# Page12_SOM_Interface.net
KiCad netlist of a schematic drawn in Altium Designer
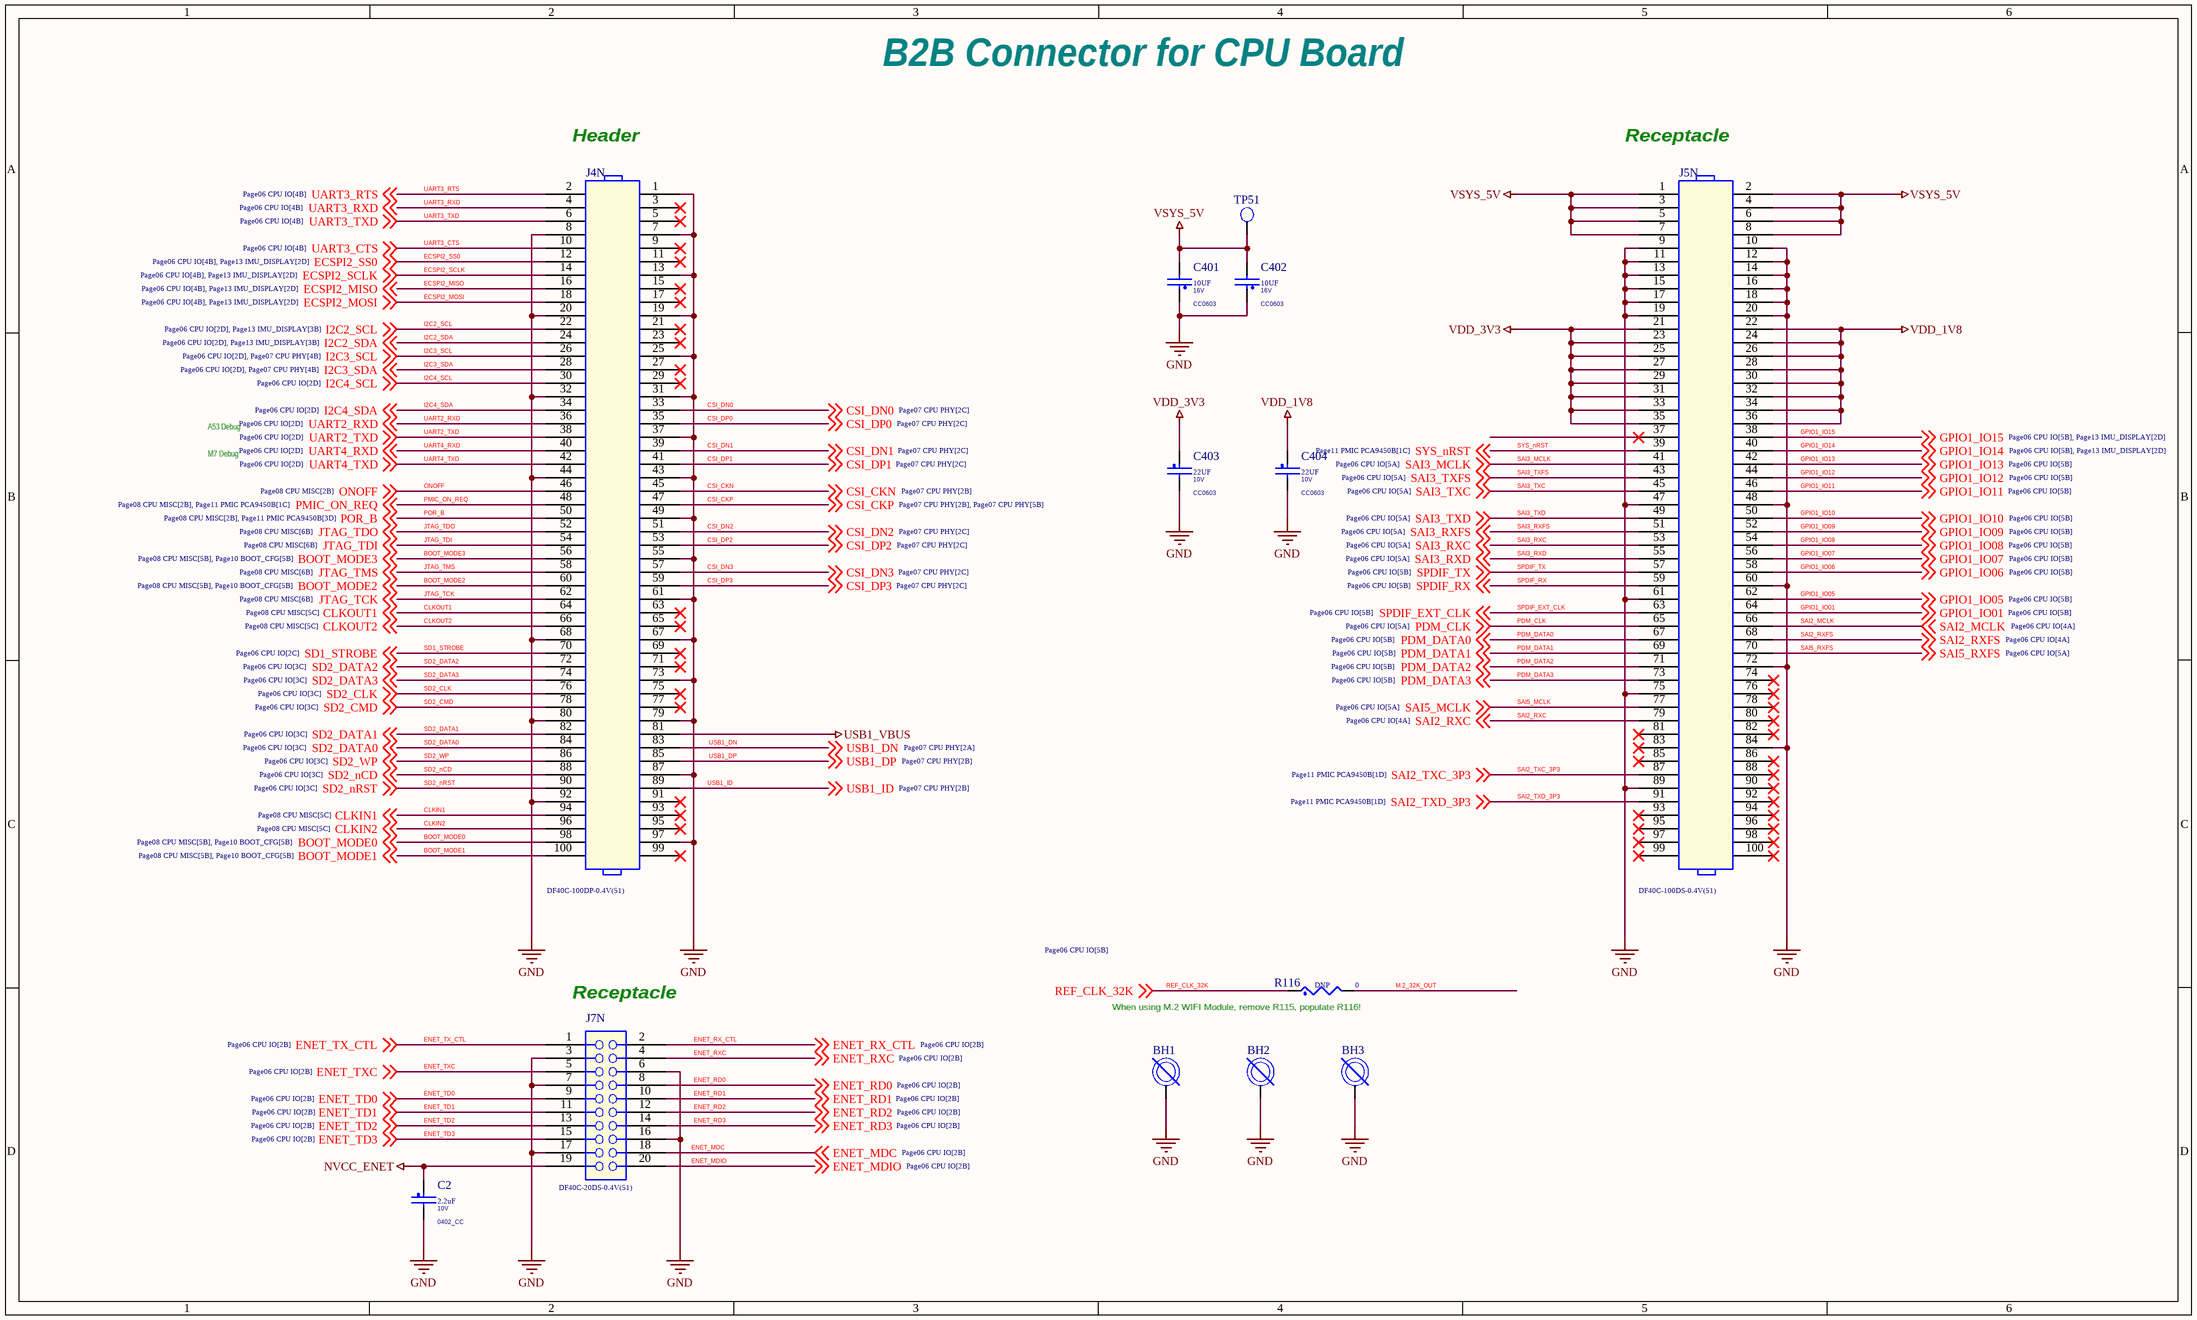
[diagram p0: Page12 SOM Interface.SchDoc]

(export (version "E")
  (design (tool "Eeschema 10.0.6"))
  (components
    (comp (ref "BH1")
      (value "MOUNTING HOLE")
      (footprint "GNDPOINT256")
      (description "MOUNTING HOLE DRILL 109 PAD 200 PLATED TH NO PART TO ORDER")
      (libsource (lib "*") (part "MOUNT_HOLE"))
    )
    (comp (ref "BH2")
      (value "MOUNTING HOLE")
      (footprint "GNDPOINT256")
      (description "MOUNTING HOLE DRILL 109 PAD 200 PLATED TH NO PART TO ORDER")
      (libsource (lib "*") (part "MOUNT_HOLE"))
    )
    (comp (ref "BH3")
      (value "MOUNTING HOLE")
      (footprint "GNDPOINT256")
      (description "MOUNTING HOLE DRILL 109 PAD 200 PLATED TH NO PART TO ORDER")
      (libsource (lib "*") (part "MOUNT_HOLE"))
    )
    (comp (ref "C2")
      (value "2.2uF")
      (footprint "0402_CC")
      (description "CAP CER 2.2uF 10V 10% X5R 0402")
      (fields
        (field (name "TOLERANCE") "10%")
        (field (name "VOLTAGE") "10V")
        (field (name "PCB FOOTPRINT") "0402_CC")
      )
      (libsource (lib "*") (part "CAP_NP"))
    )
    (comp (ref "C401")
      (value "10UF")
      (footprint "0603_CC")
      (description "CAP CER 10.0uF 16V 10% X5R 0603")
      (fields
        (field (name "PCB FOOTPRINT") "CC0603")
        (field (name "TOLERANCE") "10%")
        (field (name "VOLTAGE") "16V")
      )
      (libsource (lib "*") (part "CAP_NP"))
    )
    (comp (ref "C402")
      (value "10UF")
      (footprint "0603_CC")
      (description "CAP CER 10.0uF 16V 10% X5R 0603")
      (fields
        (field (name "PCB FOOTPRINT") "CC0603")
        (field (name "VOLTAGE") "16V")
        (field (name "TOLERANCE") "10%")
      )
      (libsource (lib "*") (part "CAP_NP"))
    )
    (comp (ref "C403")
      (value "22UF")
      (footprint "0603_CC")
      (description "CAP CER 22uF 10V 20% X5R 0603")
      (fields
        (field (name "PCB FOOTPRINT") "CC0603")
        (field (name "VOLTAGE") "10V")
        (field (name "TOLERANCE") "20%")
      )
      (libsource (lib "*") (part "CAP_NP"))
    )
    (comp (ref "C404")
      (value "22UF")
      (footprint "0603_CC")
      (description "CAP CER 22uF 10V 20% X5R 0603")
      (fields
        (field (name "PCB FOOTPRINT") "CC0603")
        (field (name "VOLTAGE") "10V")
        (field (name "TOLERANCE") "20%")
      )
      (libsource (lib "*") (part "CAP_NP"))
    )
    (comp (ref "J4N")
      (value "DF40C-100DP-0.4V(51)")
      (footprint "con100_0p4_21p7x2p05_sm")
      (description "CON 2X50 PLUG SHRD SMT 0.4MM SP 51H AU")
      (libsource (lib "") (part "HDR_2X50_M_1"))
    )
    (comp (ref "J5N")
      (value "DF40C-100DS-0.4V(51)")
      (footprint "con100_0p4_22p8x3p1_sm")
      (description "CON 2X50 SKT SHRD SMT 0.4MM SP 65H AU")
      (libsource (lib "*") (part "HDR_2X50_M"))
    )
    (comp (ref "J7N")
      (value "DF40C-20DS-0.4V(51)")
      (footprint "con20_0p4_6p8x3p1_sm")
      (description "CON 2X10 SKT SHRD SMT 0.4MM SP 63H AU")
      (libsource (lib "*") (part "CONN_HDR_10X2"))
    )
    (comp (ref "R116")
      (value "0")
      (footprint "0402_CC_RES")
      (description "RES MF ZERO OHM 1/16W 5% 0402")
      (fields
        (field (name "ASSY_OPT") "DNP")
        (field (name "VOLTAGE") "1/16W")
        (field (name "TOLERANCE") "5%")
      )
      (libsource (lib "*") (part "RES"))
    )
    (comp (ref "TP51")
      (value "TP_35MIL")
      (footprint "Test Pin")
      (description "TEST POINT PAD .035 SMT, no part to order")
      (libsource (lib "*") (part "T POINT R"))
    )
  )
  (nets
    (net (code "1") (name "/M.2_32K_OUT") (class "Default")
      (node (ref "R116") (pin "2") (pinfunction "2_2") (pintype "passive"))
    )
    (net (code "2") (name "BOOT_MODE0") (class "Default")
      (node (ref "J4N") (pin "98") (pinfunction "98_98") (pintype "passive"))
    )
    (net (code "3") (name "BOOT_MODE1") (class "Default")
      (node (ref "J4N") (pin "100") (pinfunction "100_100") (pintype "passive"))
    )
    (net (code "4") (name "BOOT_MODE2") (class "Default")
      (node (ref "J4N") (pin "60") (pinfunction "60_60") (pintype "passive"))
    )
    (net (code "5") (name "BOOT_MODE3") (class "Default")
      (node (ref "J4N") (pin "56") (pinfunction "56_56") (pintype "passive"))
    )
    (net (code "6") (name "CLKIN1") (class "Default")
      (node (ref "J4N") (pin "94") (pinfunction "94_94") (pintype "passive"))
    )
    (net (code "7") (name "CLKIN2") (class "Default")
      (node (ref "J4N") (pin "96") (pinfunction "96_96") (pintype "passive"))
    )
    (net (code "8") (name "CLKOUT1") (class "Default")
      (node (ref "J4N") (pin "64") (pinfunction "64_64") (pintype "passive"))
    )
    (net (code "9") (name "CLKOUT2") (class "Default")
      (node (ref "J4N") (pin "66") (pinfunction "66_66") (pintype "passive"))
    )
    (net (code "10") (name "CSI_CKN") (class "Default")
      (node (ref "J4N") (pin "45") (pinfunction "45_45") (pintype "passive"))
    )
    (net (code "11") (name "CSI_CKP") (class "Default")
      (node (ref "J4N") (pin "47") (pinfunction "47_47") (pintype "passive"))
    )
    (net (code "12") (name "CSI_DN0") (class "Default")
      (node (ref "J4N") (pin "33") (pinfunction "33_33") (pintype "passive"))
    )
    (net (code "13") (name "CSI_DN1") (class "Default")
      (node (ref "J4N") (pin "39") (pinfunction "39_39") (pintype "passive"))
    )
    (net (code "14") (name "CSI_DN2") (class "Default")
      (node (ref "J4N") (pin "51") (pinfunction "51_51") (pintype "passive"))
    )
    (net (code "15") (name "CSI_DN3") (class "Default")
      (node (ref "J4N") (pin "57") (pinfunction "57_57") (pintype "passive"))
    )
    (net (code "16") (name "CSI_DP0") (class "Default")
      (node (ref "J4N") (pin "35") (pinfunction "35_35") (pintype "passive"))
    )
    (net (code "17") (name "CSI_DP1") (class "Default")
      (node (ref "J4N") (pin "41") (pinfunction "41_41") (pintype "passive"))
    )
    (net (code "18") (name "CSI_DP2") (class "Default")
      (node (ref "J4N") (pin "53") (pinfunction "53_53") (pintype "passive"))
    )
    (net (code "19") (name "CSI_DP3") (class "Default")
      (node (ref "J4N") (pin "59") (pinfunction "59_59") (pintype "passive"))
    )
    (net (code "20") (name "ECSPI2_MISO") (class "Default")
      (node (ref "J4N") (pin "16") (pinfunction "16_16") (pintype "passive"))
    )
    (net (code "21") (name "ECSPI2_MOSI") (class "Default")
      (node (ref "J4N") (pin "18") (pinfunction "18_18") (pintype "passive"))
    )
    (net (code "22") (name "ECSPI2_SCLK") (class "Default")
      (node (ref "J4N") (pin "14") (pinfunction "14_14") (pintype "passive"))
    )
    (net (code "23") (name "ECSPI2_SS0") (class "Default")
      (node (ref "J4N") (pin "12") (pinfunction "12_12") (pintype "passive"))
    )
    (net (code "24") (name "ENET_MDC") (class "Default")
      (node (ref "J7N") (pin "18") (pinfunction "18_18") (pintype "passive"))
    )
    (net (code "25") (name "ENET_MDIO") (class "Default")
      (node (ref "J7N") (pin "20") (pinfunction "20_20") (pintype "passive"))
    )
    (net (code "26") (name "ENET_RD0") (class "Default")
      (node (ref "J7N") (pin "8") (pinfunction "8_8") (pintype "passive"))
    )
    (net (code "27") (name "ENET_RD1") (class "Default")
      (node (ref "J7N") (pin "10") (pinfunction "10_10") (pintype "passive"))
    )
    (net (code "28") (name "ENET_RD2") (class "Default")
      (node (ref "J7N") (pin "12") (pinfunction "12_12") (pintype "passive"))
    )
    (net (code "29") (name "ENET_RD3") (class "Default")
      (node (ref "J7N") (pin "14") (pinfunction "14_14") (pintype "passive"))
    )
    (net (code "30") (name "ENET_RXC") (class "Default")
      (node (ref "J7N") (pin "4") (pinfunction "4_4") (pintype "passive"))
    )
    (net (code "31") (name "ENET_RX_CTL") (class "Default")
      (node (ref "J7N") (pin "2") (pinfunction "2_2") (pintype "passive"))
    )
    (net (code "32") (name "ENET_TD0") (class "Default")
      (node (ref "J7N") (pin "9") (pinfunction "9_9") (pintype "passive"))
    )
    (net (code "33") (name "ENET_TD1") (class "Default")
      (node (ref "J7N") (pin "11") (pinfunction "11_11") (pintype "passive"))
    )
    (net (code "34") (name "ENET_TD2") (class "Default")
      (node (ref "J7N") (pin "13") (pinfunction "13_13") (pintype "passive"))
    )
    (net (code "35") (name "ENET_TD3") (class "Default")
      (node (ref "J7N") (pin "15") (pinfunction "15_15") (pintype "passive"))
    )
    (net (code "36") (name "ENET_TXC") (class "Default")
      (node (ref "J7N") (pin "5") (pinfunction "5_5") (pintype "passive"))
    )
    (net (code "37") (name "ENET_TX_CTL") (class "Default")
      (node (ref "J7N") (pin "1") (pinfunction "1_1") (pintype "passive"))
    )
    (net (code "38") (name "GND") (class "Default")
      (node (ref "BH1") (pin "1") (pinfunction "1_1") (pintype "passive"))
      (node (ref "BH2") (pin "1") (pinfunction "1_1") (pintype "passive"))
      (node (ref "BH3") (pin "1") (pinfunction "1_1") (pintype "passive"))
      (node (ref "C2") (pin "2") (pinfunction "2_2") (pintype "passive"))
      (node (ref "C401") (pin "1") (pinfunction "1_1") (pintype "passive"))
      (node (ref "C402") (pin "1") (pinfunction "1_1") (pintype "passive"))
      (node (ref "C403") (pin "2") (pinfunction "2_2") (pintype "passive"))
      (node (ref "C404") (pin "2") (pinfunction "2_2") (pintype "passive"))
      (node (ref "J4N") (pin "1") (pinfunction "1_1") (pintype "passive"))
      (node (ref "J4N") (pin "13") (pinfunction "13_13") (pintype "passive"))
      (node (ref "J4N") (pin "19") (pinfunction "19_19") (pintype "passive"))
      (node (ref "J4N") (pin "20") (pinfunction "20_20") (pintype "passive"))
      (node (ref "J4N") (pin "25") (pinfunction "25_25") (pintype "passive"))
      (node (ref "J4N") (pin "31") (pinfunction "31_31") (pintype "passive"))
      (node (ref "J4N") (pin "32") (pinfunction "32_32") (pintype "passive"))
      (node (ref "J4N") (pin "37") (pinfunction "37_37") (pintype "passive"))
      (node (ref "J4N") (pin "43") (pinfunction "43_43") (pintype "passive"))
      (node (ref "J4N") (pin "44") (pinfunction "44_44") (pintype "passive"))
      (node (ref "J4N") (pin "49") (pinfunction "49_49") (pintype "passive"))
      (node (ref "J4N") (pin "55") (pinfunction "55_55") (pintype "passive"))
      (node (ref "J4N") (pin "61") (pinfunction "61_61") (pintype "passive"))
      (node (ref "J4N") (pin "67") (pinfunction "67_67") (pintype "passive"))
      (node (ref "J4N") (pin "68") (pinfunction "68_68") (pintype "passive"))
      (node (ref "J4N") (pin "7") (pinfunction "7_7") (pintype "passive"))
      (node (ref "J4N") (pin "73") (pinfunction "73_73") (pintype "passive"))
      (node (ref "J4N") (pin "79") (pinfunction "79_79") (pintype "passive"))
      (node (ref "J4N") (pin "8") (pinfunction "8_8") (pintype "passive"))
      (node (ref "J4N") (pin "80") (pinfunction "80_80") (pintype "passive"))
      (node (ref "J4N") (pin "87") (pinfunction "87_87") (pintype "passive"))
      (node (ref "J4N") (pin "92") (pinfunction "92_92") (pintype "passive"))
      (node (ref "J4N") (pin "97") (pinfunction "97_97") (pintype "passive"))
      (node (ref "J5N") (pin "10") (pinfunction "10_10") (pintype "passive"))
      (node (ref "J5N") (pin "11") (pinfunction "11_11") (pintype "passive"))
      (node (ref "J5N") (pin "12") (pinfunction "12_12") (pintype "passive"))
      (node (ref "J5N") (pin "13") (pinfunction "13_13") (pintype "passive"))
      (node (ref "J5N") (pin "14") (pinfunction "14_14") (pintype "passive"))
      (node (ref "J5N") (pin "15") (pinfunction "15_15") (pintype "passive"))
      (node (ref "J5N") (pin "16") (pinfunction "16_16") (pintype "passive"))
      (node (ref "J5N") (pin "17") (pinfunction "17_17") (pintype "passive"))
      (node (ref "J5N") (pin "18") (pinfunction "18_18") (pintype "passive"))
      (node (ref "J5N") (pin "19") (pinfunction "19_19") (pintype "passive"))
      (node (ref "J5N") (pin "20") (pinfunction "20_20") (pintype "passive"))
      (node (ref "J5N") (pin "47") (pinfunction "47_47") (pintype "passive"))
      (node (ref "J5N") (pin "48") (pinfunction "48_48") (pintype "passive"))
      (node (ref "J5N") (pin "60") (pinfunction "60_60") (pintype "passive"))
      (node (ref "J5N") (pin "61") (pinfunction "61_61") (pintype "passive"))
      (node (ref "J5N") (pin "72") (pinfunction "72_72") (pintype "passive"))
      (node (ref "J5N") (pin "75") (pinfunction "75_75") (pintype "passive"))
      (node (ref "J5N") (pin "84") (pinfunction "84_84") (pintype "passive"))
      (node (ref "J5N") (pin "89") (pinfunction "89_89") (pintype "passive"))
      (node (ref "J5N") (pin "9") (pinfunction "9_9") (pintype "passive"))
      (node (ref "J7N") (pin "16") (pinfunction "16_16") (pintype "passive"))
      (node (ref "J7N") (pin "17") (pinfunction "17_17") (pintype "passive"))
      (node (ref "J7N") (pin "3") (pinfunction "3_3") (pintype "passive"))
      (node (ref "J7N") (pin "6") (pinfunction "6_6") (pintype "passive"))
      (node (ref "J7N") (pin "7") (pinfunction "7_7") (pintype "passive"))
    )
    (net (code "39") (name "GPIO1_IO01") (class "Default")
      (node (ref "J5N") (pin "64") (pinfunction "64_64") (pintype "passive"))
    )
    (net (code "40") (name "GPIO1_IO05") (class "Default")
      (node (ref "J5N") (pin "62") (pinfunction "62_62") (pintype "passive"))
    )
    (net (code "41") (name "GPIO1_IO06") (class "Default")
      (node (ref "J5N") (pin "58") (pinfunction "58_58") (pintype "passive"))
    )
    (net (code "42") (name "GPIO1_IO07") (class "Default")
      (node (ref "J5N") (pin "56") (pinfunction "56_56") (pintype "passive"))
    )
    (net (code "43") (name "GPIO1_IO08") (class "Default")
      (node (ref "J5N") (pin "54") (pinfunction "54_54") (pintype "passive"))
    )
    (net (code "44") (name "GPIO1_IO09") (class "Default")
      (node (ref "J5N") (pin "52") (pinfunction "52_52") (pintype "passive"))
    )
    (net (code "45") (name "GPIO1_IO10") (class "Default")
      (node (ref "J5N") (pin "50") (pinfunction "50_50") (pintype "passive"))
    )
    (net (code "46") (name "GPIO1_IO11") (class "Default")
      (node (ref "J5N") (pin "46") (pinfunction "46_46") (pintype "passive"))
    )
    (net (code "47") (name "GPIO1_IO12") (class "Default")
      (node (ref "J5N") (pin "44") (pinfunction "44_44") (pintype "passive"))
    )
    (net (code "48") (name "GPIO1_IO13") (class "Default")
      (node (ref "J5N") (pin "42") (pinfunction "42_42") (pintype "passive"))
    )
    (net (code "49") (name "GPIO1_IO14") (class "Default")
      (node (ref "J5N") (pin "40") (pinfunction "40_40") (pintype "passive"))
    )
    (net (code "50") (name "GPIO1_IO15") (class "Default")
      (node (ref "J5N") (pin "38") (pinfunction "38_38") (pintype "passive"))
    )
    (net (code "51") (name "I2C2_SCL") (class "Default")
      (node (ref "J4N") (pin "22") (pinfunction "22_22") (pintype "passive"))
    )
    (net (code "52") (name "I2C2_SDA") (class "Default")
      (node (ref "J4N") (pin "24") (pinfunction "24_24") (pintype "passive"))
    )
    (net (code "53") (name "I2C3_SCL") (class "Default")
      (node (ref "J4N") (pin "26") (pinfunction "26_26") (pintype "passive"))
    )
    (net (code "54") (name "I2C3_SDA") (class "Default")
      (node (ref "J4N") (pin "28") (pinfunction "28_28") (pintype "passive"))
    )
    (net (code "55") (name "I2C4_SCL") (class "Default")
      (node (ref "J4N") (pin "30") (pinfunction "30_30") (pintype "passive"))
    )
    (net (code "56") (name "I2C4_SDA") (class "Default")
      (node (ref "J4N") (pin "34") (pinfunction "34_34") (pintype "passive"))
    )
    (net (code "57") (name "JTAG_TCK") (class "Default")
      (node (ref "J4N") (pin "62") (pinfunction "62_62") (pintype "passive"))
    )
    (net (code "58") (name "JTAG_TDI") (class "Default")
      (node (ref "J4N") (pin "54") (pinfunction "54_54") (pintype "passive"))
    )
    (net (code "59") (name "JTAG_TDO") (class "Default")
      (node (ref "J4N") (pin "52") (pinfunction "52_52") (pintype "passive"))
    )
    (net (code "60") (name "JTAG_TMS") (class "Default")
      (node (ref "J4N") (pin "58") (pinfunction "58_58") (pintype "passive"))
    )
    (net (code "61") (name "NVCC_ENET") (class "Default")
      (node (ref "C2") (pin "1") (pinfunction "1_1") (pintype "passive"))
      (node (ref "J7N") (pin "19") (pinfunction "19_19") (pintype "passive"))
    )
    (net (code "62") (name "ONOFF") (class "Default")
      (node (ref "J4N") (pin "46") (pinfunction "46_46") (pintype "passive"))
    )
    (net (code "63") (name "PDM_CLK") (class "Default")
      (node (ref "J5N") (pin "65") (pinfunction "65_65") (pintype "passive"))
    )
    (net (code "64") (name "PDM_DATA0") (class "Default")
      (node (ref "J5N") (pin "67") (pinfunction "67_67") (pintype "passive"))
    )
    (net (code "65") (name "PDM_DATA1") (class "Default")
      (node (ref "J5N") (pin "69") (pinfunction "69_69") (pintype "passive"))
    )
    (net (code "66") (name "PDM_DATA2") (class "Default")
      (node (ref "J5N") (pin "71") (pinfunction "71_71") (pintype "passive"))
    )
    (net (code "67") (name "PDM_DATA3") (class "Default")
      (node (ref "J5N") (pin "73") (pinfunction "73_73") (pintype "passive"))
    )
    (net (code "68") (name "PMIC_ON_REQ") (class "Default")
      (node (ref "J4N") (pin "48") (pinfunction "48_48") (pintype "passive"))
    )
    (net (code "69") (name "POR_B") (class "Default")
      (node (ref "J4N") (pin "50") (pinfunction "50_50") (pintype "passive"))
    )
    (net (code "70") (name "REF_CLK_32K") (class "Default")
      (node (ref "R116") (pin "1") (pinfunction "1_1") (pintype "passive"))
    )
    (net (code "71") (name "SAI2_MCLK") (class "Default")
      (node (ref "J5N") (pin "66") (pinfunction "66_66") (pintype "passive"))
    )
    (net (code "72") (name "SAI2_RXC") (class "Default")
      (node (ref "J5N") (pin "79") (pinfunction "79_79") (pintype "passive"))
    )
    (net (code "73") (name "SAI2_RXFS") (class "Default")
      (node (ref "J5N") (pin "68") (pinfunction "68_68") (pintype "passive"))
    )
    (net (code "74") (name "SAI2_TXC_3P3") (class "Default")
      (node (ref "J5N") (pin "87") (pinfunction "87_87") (pintype "passive"))
    )
    (net (code "75") (name "SAI2_TXD_3P3") (class "Default")
      (node (ref "J5N") (pin "91") (pinfunction "91_91") (pintype "passive"))
    )
    (net (code "76") (name "SAI3_MCLK") (class "Default")
      (node (ref "J5N") (pin "41") (pinfunction "41_41") (pintype "passive"))
    )
    (net (code "77") (name "SAI3_RXC") (class "Default")
      (node (ref "J5N") (pin "53") (pinfunction "53_53") (pintype "passive"))
    )
    (net (code "78") (name "SAI3_RXD") (class "Default")
      (node (ref "J5N") (pin "55") (pinfunction "55_55") (pintype "passive"))
    )
    (net (code "79") (name "SAI3_RXFS") (class "Default")
      (node (ref "J5N") (pin "51") (pinfunction "51_51") (pintype "passive"))
    )
    (net (code "80") (name "SAI3_TXC") (class "Default")
      (node (ref "J5N") (pin "45") (pinfunction "45_45") (pintype "passive"))
    )
    (net (code "81") (name "SAI3_TXD") (class "Default")
      (node (ref "J5N") (pin "49") (pinfunction "49_49") (pintype "passive"))
    )
    (net (code "82") (name "SAI3_TXFS") (class "Default")
      (node (ref "J5N") (pin "43") (pinfunction "43_43") (pintype "passive"))
    )
    (net (code "83") (name "SAI5_MCLK") (class "Default")
      (node (ref "J5N") (pin "77") (pinfunction "77_77") (pintype "passive"))
    )
    (net (code "84") (name "SAI5_RXFS") (class "Default")
      (node (ref "J5N") (pin "70") (pinfunction "70_70") (pintype "passive"))
    )
    (net (code "85") (name "SD1_STROBE") (class "Default")
      (node (ref "J4N") (pin "70") (pinfunction "70_70") (pintype "passive"))
    )
    (net (code "86") (name "SD2_CLK") (class "Default")
      (node (ref "J4N") (pin "76") (pinfunction "76_76") (pintype "passive"))
    )
    (net (code "87") (name "SD2_CMD") (class "Default")
      (node (ref "J4N") (pin "78") (pinfunction "78_78") (pintype "passive"))
    )
    (net (code "88") (name "SD2_DATA0") (class "Default")
      (node (ref "J4N") (pin "84") (pinfunction "84_84") (pintype "passive"))
    )
    (net (code "89") (name "SD2_DATA1") (class "Default")
      (node (ref "J4N") (pin "82") (pinfunction "82_82") (pintype "passive"))
    )
    (net (code "90") (name "SD2_DATA2") (class "Default")
      (node (ref "J4N") (pin "72") (pinfunction "72_72") (pintype "passive"))
    )
    (net (code "91") (name "SD2_DATA3") (class "Default")
      (node (ref "J4N") (pin "74") (pinfunction "74_74") (pintype "passive"))
    )
    (net (code "92") (name "SD2_WP") (class "Default")
      (node (ref "J4N") (pin "86") (pinfunction "86_86") (pintype "passive"))
    )
    (net (code "93") (name "SD2_nCD") (class "Default")
      (node (ref "J4N") (pin "88") (pinfunction "88_88") (pintype "passive"))
    )
    (net (code "94") (name "SD2_nRST") (class "Default")
      (node (ref "J4N") (pin "90") (pinfunction "90_90") (pintype "passive"))
    )
    (net (code "95") (name "SPDIF_EXT_CLK") (class "Default")
      (node (ref "J5N") (pin "63") (pinfunction "63_63") (pintype "passive"))
    )
    (net (code "96") (name "SPDIF_RX") (class "Default")
      (node (ref "J5N") (pin "59") (pinfunction "59_59") (pintype "passive"))
    )
    (net (code "97") (name "SPDIF_TX") (class "Default")
      (node (ref "J5N") (pin "57") (pinfunction "57_57") (pintype "passive"))
    )
    (net (code "98") (name "SYS_nRST") (class "Default")
      (node (ref "J5N") (pin "39") (pinfunction "39_39") (pintype "passive"))
    )
    (net (code "99") (name "UART2_RXD") (class "Default")
      (node (ref "J4N") (pin "36") (pinfunction "36_36") (pintype "passive"))
    )
    (net (code "100") (name "UART2_TXD") (class "Default")
      (node (ref "J4N") (pin "38") (pinfunction "38_38") (pintype "passive"))
    )
    (net (code "101") (name "UART3_CTS") (class "Default")
      (node (ref "J4N") (pin "10") (pinfunction "10_10") (pintype "passive"))
    )
    (net (code "102") (name "UART3_RTS") (class "Default")
      (node (ref "J4N") (pin "2") (pinfunction "2_2") (pintype "passive"))
    )
    (net (code "103") (name "UART3_RXD") (class "Default")
      (node (ref "J4N") (pin "4") (pinfunction "4_4") (pintype "passive"))
    )
    (net (code "104") (name "UART3_TXD") (class "Default")
      (node (ref "J4N") (pin "6") (pinfunction "6_6") (pintype "passive"))
    )
    (net (code "105") (name "UART4_RXD") (class "Default")
      (node (ref "J4N") (pin "40") (pinfunction "40_40") (pintype "passive"))
    )
    (net (code "106") (name "UART4_TXD") (class "Default")
      (node (ref "J4N") (pin "42") (pinfunction "42_42") (pintype "passive"))
    )
    (net (code "107") (name "USB1_DN") (class "Default")
      (node (ref "J4N") (pin "83") (pinfunction "83_83") (pintype "passive"))
    )
    (net (code "108") (name "USB1_DP") (class "Default")
      (node (ref "J4N") (pin "85") (pinfunction "85_85") (pintype "passive"))
    )
    (net (code "109") (name "USB1_ID") (class "Default")
      (node (ref "J4N") (pin "89") (pinfunction "89_89") (pintype "passive"))
    )
    (net (code "110") (name "USB1_VBUS") (class "Default")
      (node (ref "J4N") (pin "81") (pinfunction "81_81") (pintype "passive"))
    )
    (net (code "111") (name "VDD_1V8") (class "Default")
      (node (ref "C404") (pin "1") (pinfunction "1_1") (pintype "passive"))
      (node (ref "J5N") (pin "22") (pinfunction "22_22") (pintype "passive"))
      (node (ref "J5N") (pin "24") (pinfunction "24_24") (pintype "passive"))
      (node (ref "J5N") (pin "26") (pinfunction "26_26") (pintype "passive"))
      (node (ref "J5N") (pin "28") (pinfunction "28_28") (pintype "passive"))
      (node (ref "J5N") (pin "30") (pinfunction "30_30") (pintype "passive"))
      (node (ref "J5N") (pin "32") (pinfunction "32_32") (pintype "passive"))
      (node (ref "J5N") (pin "34") (pinfunction "34_34") (pintype "passive"))
      (node (ref "J5N") (pin "36") (pinfunction "36_36") (pintype "passive"))
    )
    (net (code "112") (name "VDD_3V3") (class "Default")
      (node (ref "C403") (pin "1") (pinfunction "1_1") (pintype "passive"))
      (node (ref "J5N") (pin "21") (pinfunction "21_21") (pintype "passive"))
      (node (ref "J5N") (pin "23") (pinfunction "23_23") (pintype "passive"))
      (node (ref "J5N") (pin "25") (pinfunction "25_25") (pintype "passive"))
      (node (ref "J5N") (pin "27") (pinfunction "27_27") (pintype "passive"))
      (node (ref "J5N") (pin "29") (pinfunction "29_29") (pintype "passive"))
      (node (ref "J5N") (pin "31") (pinfunction "31_31") (pintype "passive"))
      (node (ref "J5N") (pin "33") (pinfunction "33_33") (pintype "passive"))
      (node (ref "J5N") (pin "35") (pinfunction "35_35") (pintype "passive"))
    )
    (net (code "113") (name "VSYS_5V") (class "Default")
      (node (ref "C401") (pin "2") (pinfunction "2_2") (pintype "passive"))
      (node (ref "C402") (pin "2") (pinfunction "2_2") (pintype "passive"))
      (node (ref "J5N") (pin "1") (pinfunction "1_1") (pintype "passive"))
      (node (ref "J5N") (pin "2") (pinfunction "2_2") (pintype "passive"))
      (node (ref "J5N") (pin "3") (pinfunction "3_3") (pintype "passive"))
      (node (ref "J5N") (pin "4") (pinfunction "4_4") (pintype "passive"))
      (node (ref "J5N") (pin "5") (pinfunction "5_5") (pintype "passive"))
      (node (ref "J5N") (pin "6") (pinfunction "6_6") (pintype "passive"))
      (node (ref "J5N") (pin "7") (pinfunction "7_7") (pintype "passive"))
      (node (ref "J5N") (pin "8") (pinfunction "8_8") (pintype "passive"))
      (node (ref "TP51") (pin "1") (pinfunction "TP_1") (pintype "passive"))
    )
    (net (code "114") (name "unconnected-(J4N-Pad3)") (class "Default")
      (node (ref "J4N") (pin "3") (pinfunction "3_3") (pintype "passive+no_connect"))
    )
    (net (code "115") (name "unconnected-(J4N-Pad5)") (class "Default")
      (node (ref "J4N") (pin "5") (pinfunction "5_5") (pintype "passive+no_connect"))
    )
    (net (code "116") (name "unconnected-(J4N-Pad9)") (class "Default")
      (node (ref "J4N") (pin "9") (pinfunction "9_9") (pintype "passive+no_connect"))
    )
    (net (code "117") (name "unconnected-(J4N-Pad11)") (class "Default")
      (node (ref "J4N") (pin "11") (pinfunction "11_11") (pintype "passive+no_connect"))
    )
    (net (code "118") (name "unconnected-(J4N-Pad15)") (class "Default")
      (node (ref "J4N") (pin "15") (pinfunction "15_15") (pintype "passive+no_connect"))
    )
    (net (code "119") (name "unconnected-(J4N-Pad17)") (class "Default")
      (node (ref "J4N") (pin "17") (pinfunction "17_17") (pintype "passive+no_connect"))
    )
    (net (code "120") (name "unconnected-(J4N-Pad21)") (class "Default")
      (node (ref "J4N") (pin "21") (pinfunction "21_21") (pintype "passive+no_connect"))
    )
    (net (code "121") (name "unconnected-(J4N-Pad23)") (class "Default")
      (node (ref "J4N") (pin "23") (pinfunction "23_23") (pintype "passive+no_connect"))
    )
    (net (code "122") (name "unconnected-(J4N-Pad27)") (class "Default")
      (node (ref "J4N") (pin "27") (pinfunction "27_27") (pintype "passive+no_connect"))
    )
    (net (code "123") (name "unconnected-(J4N-Pad29)") (class "Default")
      (node (ref "J4N") (pin "29") (pinfunction "29_29") (pintype "passive+no_connect"))
    )
    (net (code "124") (name "unconnected-(J4N-Pad63)") (class "Default")
      (node (ref "J4N") (pin "63") (pinfunction "63_63") (pintype "passive+no_connect"))
    )
    (net (code "125") (name "unconnected-(J4N-Pad65)") (class "Default")
      (node (ref "J4N") (pin "65") (pinfunction "65_65") (pintype "passive+no_connect"))
    )
    (net (code "126") (name "unconnected-(J4N-Pad69)") (class "Default")
      (node (ref "J4N") (pin "69") (pinfunction "69_69") (pintype "passive+no_connect"))
    )
    (net (code "127") (name "unconnected-(J4N-Pad71)") (class "Default")
      (node (ref "J4N") (pin "71") (pinfunction "71_71") (pintype "passive+no_connect"))
    )
    (net (code "128") (name "unconnected-(J4N-Pad75)") (class "Default")
      (node (ref "J4N") (pin "75") (pinfunction "75_75") (pintype "passive+no_connect"))
    )
    (net (code "129") (name "unconnected-(J4N-Pad77)") (class "Default")
      (node (ref "J4N") (pin "77") (pinfunction "77_77") (pintype "passive+no_connect"))
    )
    (net (code "130") (name "unconnected-(J4N-Pad91)") (class "Default")
      (node (ref "J4N") (pin "91") (pinfunction "91_91") (pintype "passive+no_connect"))
    )
    (net (code "131") (name "unconnected-(J4N-Pad93)") (class "Default")
      (node (ref "J4N") (pin "93") (pinfunction "93_93") (pintype "passive+no_connect"))
    )
    (net (code "132") (name "unconnected-(J4N-Pad95)") (class "Default")
      (node (ref "J4N") (pin "95") (pinfunction "95_95") (pintype "passive+no_connect"))
    )
    (net (code "133") (name "unconnected-(J4N-Pad99)") (class "Default")
      (node (ref "J4N") (pin "99") (pinfunction "99_99") (pintype "passive+no_connect"))
    )
    (net (code "134") (name "unconnected-(J5N-Pad37)") (class "Default")
      (node (ref "J5N") (pin "37") (pinfunction "37_37") (pintype "passive+no_connect"))
    )
    (net (code "135") (name "unconnected-(J5N-Pad74)") (class "Default")
      (node (ref "J5N") (pin "74") (pinfunction "74_74") (pintype "passive+no_connect"))
    )
    (net (code "136") (name "unconnected-(J5N-Pad76)") (class "Default")
      (node (ref "J5N") (pin "76") (pinfunction "76_76") (pintype "passive+no_connect"))
    )
    (net (code "137") (name "unconnected-(J5N-Pad78)") (class "Default")
      (node (ref "J5N") (pin "78") (pinfunction "78_78") (pintype "passive+no_connect"))
    )
    (net (code "138") (name "unconnected-(J5N-Pad80)") (class "Default")
      (node (ref "J5N") (pin "80") (pinfunction "80_80") (pintype "passive+no_connect"))
    )
    (net (code "139") (name "unconnected-(J5N-Pad81)") (class "Default")
      (node (ref "J5N") (pin "81") (pinfunction "81_81") (pintype "passive+no_connect"))
    )
    (net (code "140") (name "unconnected-(J5N-Pad82)") (class "Default")
      (node (ref "J5N") (pin "82") (pinfunction "82_82") (pintype "passive+no_connect"))
    )
    (net (code "141") (name "unconnected-(J5N-Pad83)") (class "Default")
      (node (ref "J5N") (pin "83") (pinfunction "83_83") (pintype "passive+no_connect"))
    )
    (net (code "142") (name "unconnected-(J5N-Pad85)") (class "Default")
      (node (ref "J5N") (pin "85") (pinfunction "85_85") (pintype "passive+no_connect"))
    )
    (net (code "143") (name "unconnected-(J5N-Pad86)") (class "Default")
      (node (ref "J5N") (pin "86") (pinfunction "86_86") (pintype "passive+no_connect"))
    )
    (net (code "144") (name "unconnected-(J5N-Pad88)") (class "Default")
      (node (ref "J5N") (pin "88") (pinfunction "88_88") (pintype "passive+no_connect"))
    )
    (net (code "145") (name "unconnected-(J5N-Pad90)") (class "Default")
      (node (ref "J5N") (pin "90") (pinfunction "90_90") (pintype "passive+no_connect"))
    )
    (net (code "146") (name "unconnected-(J5N-Pad92)") (class "Default")
      (node (ref "J5N") (pin "92") (pinfunction "92_92") (pintype "passive+no_connect"))
    )
    (net (code "147") (name "unconnected-(J5N-Pad93)") (class "Default")
      (node (ref "J5N") (pin "93") (pinfunction "93_93") (pintype "passive+no_connect"))
    )
    (net (code "148") (name "unconnected-(J5N-Pad94)") (class "Default")
      (node (ref "J5N") (pin "94") (pinfunction "94_94") (pintype "passive+no_connect"))
    )
    (net (code "149") (name "unconnected-(J5N-Pad95)") (class "Default")
      (node (ref "J5N") (pin "95") (pinfunction "95_95") (pintype "passive+no_connect"))
    )
    (net (code "150") (name "unconnected-(J5N-Pad96)") (class "Default")
      (node (ref "J5N") (pin "96") (pinfunction "96_96") (pintype "passive+no_connect"))
    )
    (net (code "151") (name "unconnected-(J5N-Pad97)") (class "Default")
      (node (ref "J5N") (pin "97") (pinfunction "97_97") (pintype "passive+no_connect"))
    )
    (net (code "152") (name "unconnected-(J5N-Pad98)") (class "Default")
      (node (ref "J5N") (pin "98") (pinfunction "98_98") (pintype "passive+no_connect"))
    )
    (net (code "153") (name "unconnected-(J5N-Pad99)") (class "Default")
      (node (ref "J5N") (pin "99") (pinfunction "99_99") (pintype "passive+no_connect"))
    )
    (net (code "154") (name "unconnected-(J5N-Pad100)") (class "Default")
      (node (ref "J5N") (pin "100") (pinfunction "100_100") (pintype "passive+no_connect"))
    )
  )
)
